# Port.net
KiCad netlist of a schematic drawn in Altium Designer
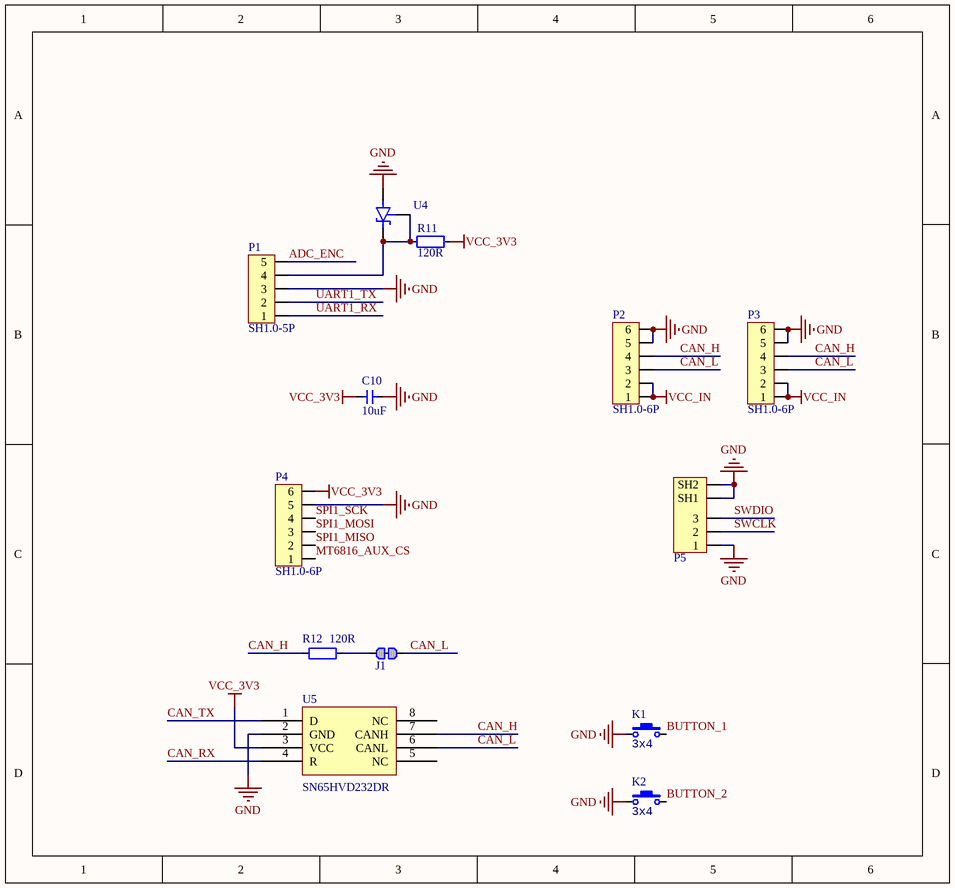
[diagram p0: Port.SchDoc]

(export (version "E")
  (design (tool "Eeschema 10.0.6"))
  (components
    (comp (ref "C10")
      (value "10uF")
      (footprint "CAP_0402")
      (description "Capacitor")
      (libsource (lib "MyPcbLib") (part "电容-0402"))
    )
    (comp (ref "J1")
      (value "跳线")
      (footprint "0402-0R")
      (description "Resistor")
      (fields (field (name "PUBLISHER") "Altium Limited"))
      (libsource (lib "MyPcbLib") (part "跳线"))
    )
    (comp (ref "K1")
      (value "3x4")
      (footprint "ButtonTACT_3x4x2_180")
      (description "Button")
      (fields (field (name "Comment") "TACT 2P"))
      (libsource (lib "KitSprout") (part "ButtonTACT_3x4x2_180"))
    )
    (comp (ref "K2")
      (value "3x4")
      (footprint "ButtonTACT_3x4x2_180")
      (description "Button")
      (fields (field (name "Comment") "TACT 2P"))
      (libsource (lib "KitSprout") (part "ButtonTACT_3x4x2_180"))
    )
    (comp (ref "P1") (value "SH1.0-5P") (footprint "SH1.0-5P") (libsource (lib "MyPcbLib") (part "SH1.0-5P")))
    (comp (ref "P2") (value "SH1.0-6P") (footprint "SH1.0-6P") (libsource (lib "MyPcbLib") (part "SH1.0-6P")))
    (comp (ref "P3") (value "SH1.0-6P") (footprint "SH1.0-6P") (libsource (lib "MyPcbLib") (part "SH1.0-6P")))
    (comp (ref "P4") (value "SH1.0-6P") (footprint "SH1.0-6P") (libsource (lib "MyPcbLib") (part "SH1.0-6P")))
    (comp (ref "P5")
      (value "SH1.0-3P")
      (footprint "SH1.0-3P")
      (description "Header")
      (libsource (lib "MyPcbLib") (part "SH1.0-3P"))
    )
    (comp (ref "R11")
      (value "120R")
      (footprint "RES_0402")
      (description "Resistor")
      (libsource (lib "MyPcbLib") (part "电阻-0402"))
    )
    (comp (ref "R12")
      (value "120R")
      (footprint "RES_0402")
      (description "Resistor")
      (libsource (lib "") (part "电阻-0402_1"))
    )
    (comp (ref "U4")
      (value "TL431IDBZT")
      (footprint "SOT23-3")
      (description "Adjustable precision shunt regulator 3-SOT-23 -40 to 85")
      (fields (field (name "MF") "Texas Instruments"))
      (libsource (lib "MyPcbLib") (part "TL431IDBZT"))
    )
    (comp (ref "U5")
      (value "SN65HVD232D")
      (footprint "SO-8")
      (fields
        (field (name "MANUFACTURER") "Texas Instruments")
        (field (name "MANUFACTURER PART NUMBER") "SN65HVD232DR")
      )
      (libsource (lib "MyPcbLib") (part "SN65HVD232D"))
    )
  )
  (nets
    (net (code "1") (name "/ADC_ENC") (class "Default")
      (node (ref "P1") (pin "5") (pinfunction "5_5") (pintype "passive"))
    )
    (net (code "2") (name "/BUTTON_1") (class "Default")
      (node (ref "K1") (pin "2") (pinfunction "2_2") (pintype "passive"))
    )
    (net (code "3") (name "/BUTTON_2") (class "Default")
      (node (ref "K2") (pin "2") (pinfunction "2_2") (pintype "passive"))
    )
    (net (code "4") (name "/CAN_H") (class "Default")
      (node (ref "P2") (pin "4") (pinfunction "4_4") (pintype "passive"))
      (node (ref "P3") (pin "4") (pinfunction "4_4") (pintype "passive"))
      (node (ref "R12") (pin "1") (pinfunction "1_1") (pintype "passive"))
      (node (ref "U5") (pin "7") (pinfunction "CANH_7") (pintype "passive"))
    )
    (net (code "5") (name "/CAN_L") (class "Default")
      (node (ref "J1") (pin "2") (pinfunction "2_2") (pintype "passive"))
      (node (ref "P2") (pin "3") (pinfunction "3_3") (pintype "passive"))
      (node (ref "P3") (pin "3") (pinfunction "3_3") (pintype "passive"))
      (node (ref "U5") (pin "6") (pinfunction "CANL_6") (pintype "passive"))
    )
    (net (code "6") (name "/CAN_RX") (class "Default")
      (node (ref "U5") (pin "4") (pinfunction "R_4") (pintype "passive"))
    )
    (net (code "7") (name "/CAN_TX") (class "Default")
      (node (ref "U5") (pin "1") (pinfunction "D_1") (pintype "passive"))
    )
    (net (code "8") (name "/MT6816_AUX_CS") (class "Default")
      (node (ref "P4") (pin "1") (pinfunction "1_1") (pintype "passive"))
    )
    (net (code "9") (name "/SPI1_MISO") (class "Default")
      (node (ref "P4") (pin "2") (pinfunction "2_2") (pintype "passive"))
    )
    (net (code "10") (name "/SPI1_MOSI") (class "Default")
      (node (ref "P4") (pin "3") (pinfunction "3_3") (pintype "passive"))
    )
    (net (code "11") (name "/SPI1_SCK") (class "Default")
      (node (ref "P4") (pin "4") (pinfunction "4_4") (pintype "passive"))
    )
    (net (code "12") (name "/SWCLK") (class "Default")
      (node (ref "P5") (pin "2") (pinfunction "2_2") (pintype "passive"))
    )
    (net (code "13") (name "/SWDIO") (class "Default")
      (node (ref "P5") (pin "3") (pinfunction "3_3") (pintype "passive"))
    )
    (net (code "14") (name "/UART1_RX") (class "Default")
      (node (ref "P1") (pin "1") (pinfunction "1_1") (pintype "passive"))
    )
    (net (code "15") (name "/UART1_TX") (class "Default")
      (node (ref "P1") (pin "2") (pinfunction "2_2") (pintype "passive"))
    )
    (net (code "16") (name "GND") (class "Default")
      (node (ref "C10") (pin "1") (pinfunction "1_1") (pintype "passive"))
      (node (ref "K1") (pin "1") (pinfunction "1_1") (pintype "passive"))
      (node (ref "K2") (pin "1") (pinfunction "1_1") (pintype "passive"))
      (node (ref "P1") (pin "3") (pinfunction "3_3") (pintype "passive"))
      (node (ref "P2") (pin "5") (pinfunction "5_5") (pintype "passive"))
      (node (ref "P2") (pin "6") (pinfunction "6_6") (pintype "passive"))
      (node (ref "P3") (pin "5") (pinfunction "5_5") (pintype "passive"))
      (node (ref "P3") (pin "6") (pinfunction "6_6") (pintype "passive"))
      (node (ref "P4") (pin "5") (pinfunction "5_5") (pintype "passive"))
      (node (ref "P5") (pin "1") (pinfunction "1_1") (pintype "passive"))
      (node (ref "P5") (pin "SH1") (pinfunction "SH1_SH1") (pintype "passive"))
      (node (ref "P5") (pin "SH2") (pinfunction "SH2_SH2") (pintype "passive"))
      (node (ref "U4") (pin "3") (pinfunction "ANODE_3") (pintype "passive"))
      (node (ref "U5") (pin "2") (pinfunction "GND_2") (pintype "passive"))
    )
    (net (code "17") (name "Net-(J1-Pad1)") (class "Default")
      (node (ref "J1") (pin "1") (pinfunction "1_1") (pintype "passive"))
      (node (ref "R12") (pin "2") (pinfunction "2_2") (pintype "passive"))
    )
    (net (code "18") (name "Net-(U4-CATHODE)") (class "Default")
      (node (ref "P1") (pin "4") (pinfunction "4_4") (pintype "passive"))
      (node (ref "R11") (pin "2") (pinfunction "2_2") (pintype "passive"))
      (node (ref "U4") (pin "1") (pinfunction "CATHODE_1") (pintype "passive"))
      (node (ref "U4") (pin "2") (pinfunction "REF_2") (pintype "passive"))
    )
    (net (code "19") (name "VCC_3V3") (class "Default")
      (node (ref "C10") (pin "2") (pinfunction "2_2") (pintype "passive"))
      (node (ref "P4") (pin "6") (pinfunction "6_6") (pintype "passive"))
      (node (ref "R11") (pin "1") (pinfunction "1_1") (pintype "passive"))
      (node (ref "U5") (pin "3") (pinfunction "VCC_3") (pintype "passive"))
    )
    (net (code "20") (name "VCC_IN") (class "Default")
      (node (ref "P2") (pin "1") (pinfunction "1_1") (pintype "passive"))
      (node (ref "P2") (pin "2") (pinfunction "2_2") (pintype "passive"))
      (node (ref "P3") (pin "1") (pinfunction "1_1") (pintype "passive"))
      (node (ref "P3") (pin "2") (pinfunction "2_2") (pintype "passive"))
    )
    (net (code "21") (name "unconnected-(U5-NC-Pad5)") (class "Default")
      (node (ref "U5") (pin "5") (pinfunction "NC_5") (pintype "passive"))
    )
    (net (code "22") (name "unconnected-(U5-NC-Pad8)") (class "Default")
      (node (ref "U5") (pin "8") (pinfunction "NC_8") (pintype "passive"))
    )
  )
)
